# OnOnfre_dual_mola_ssr_rev3_2.net
KiCad netlist of a schematic drawn in EAGLE
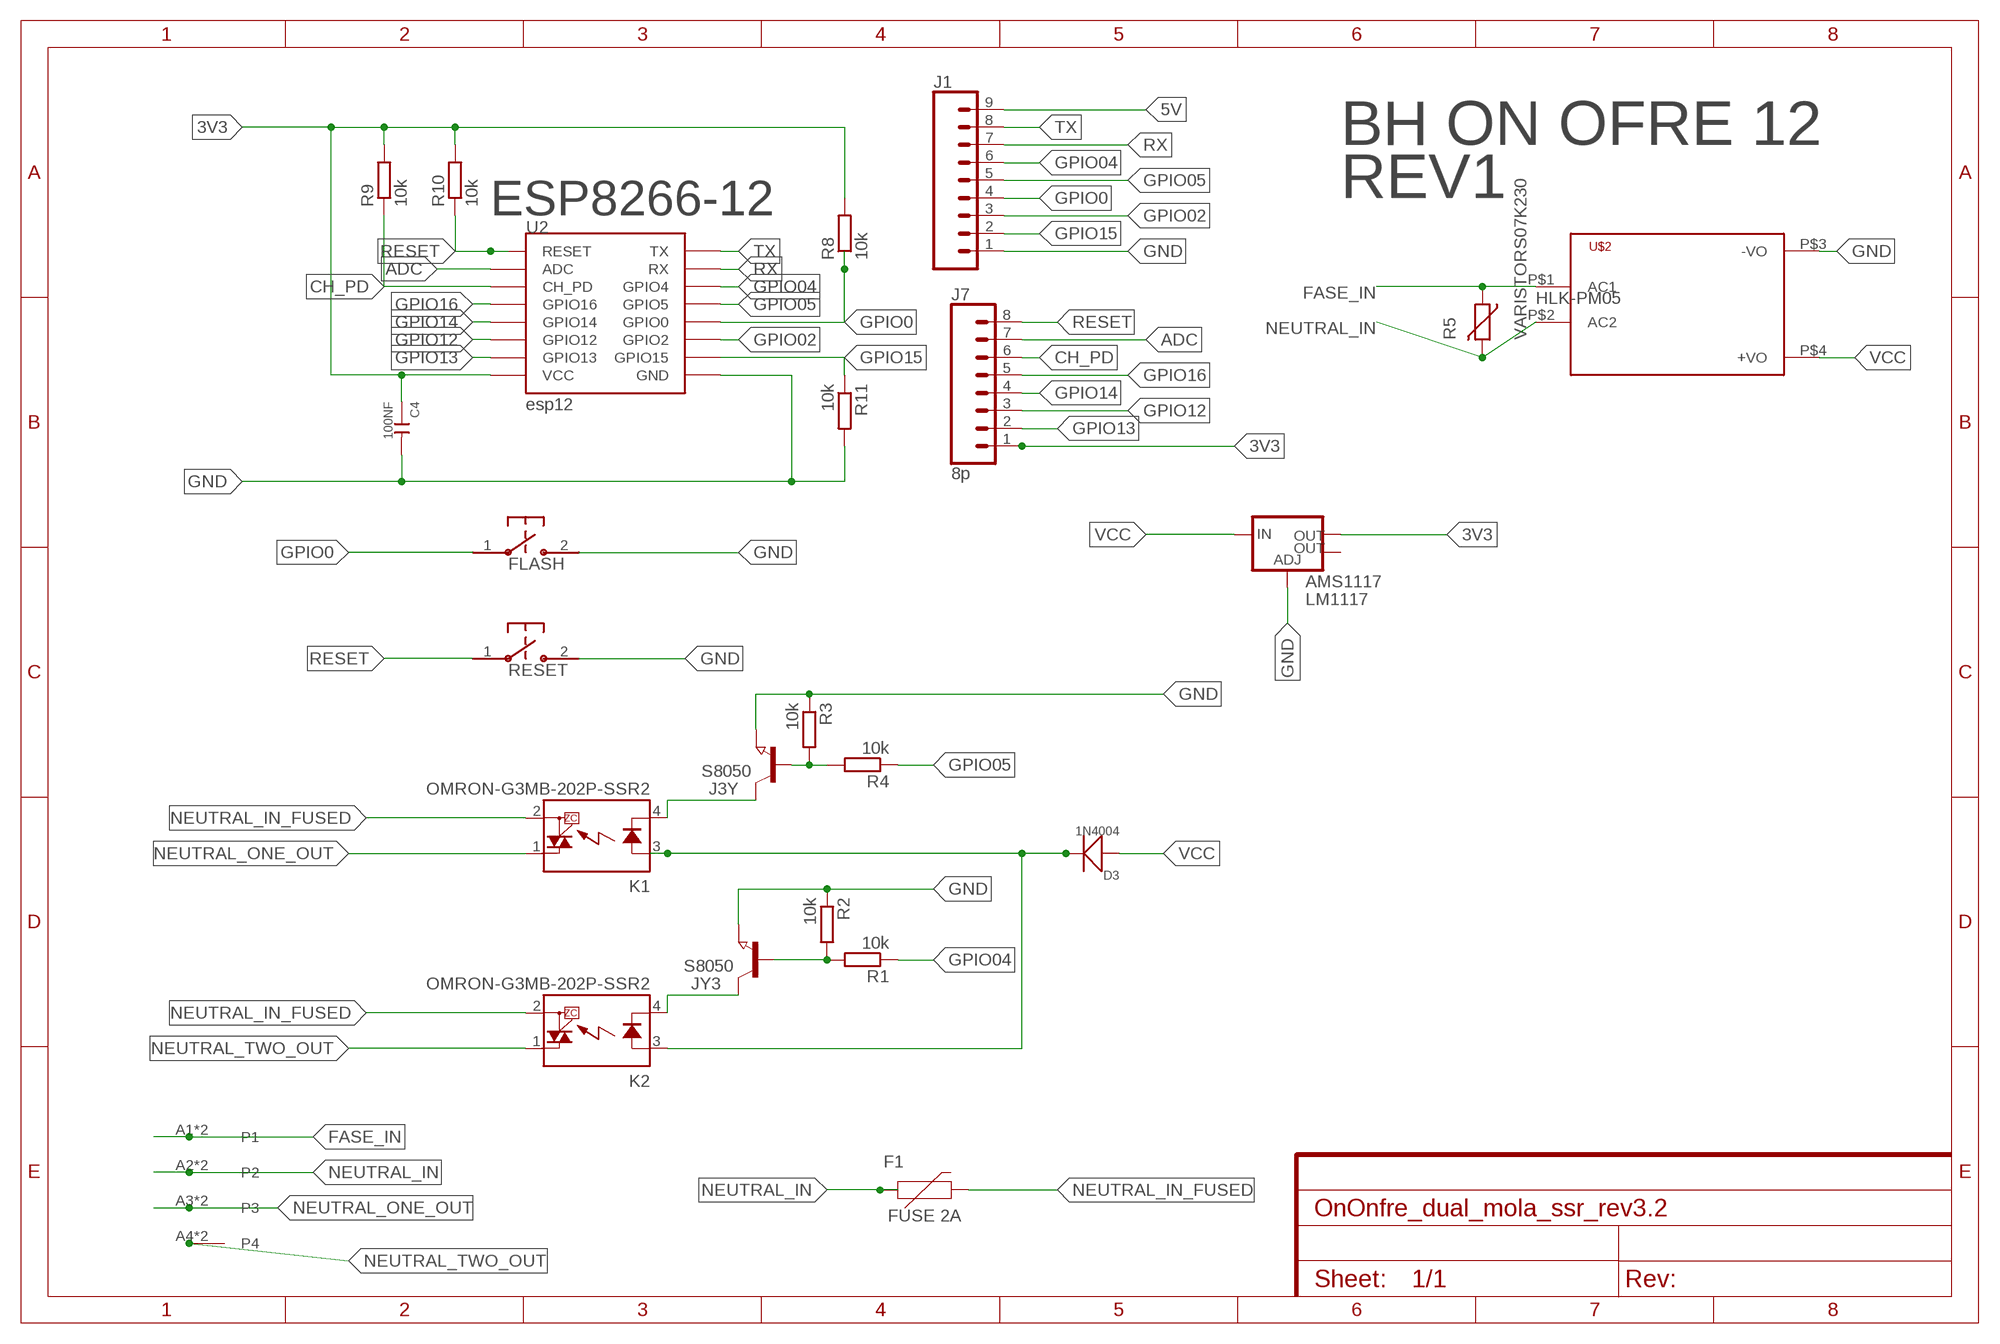
[diagram p0: schematic, sheet 1]

(export (version "E")
  (design (tool "Eeschema 10.0.6"))
  (components
    (comp (ref "AMS1117")
      (value "LM1117")
      (footprint "eagle-import:SOT223")
      (libsource (lib "eagle-import") (part "V_REG_LM1117SOT223"))
    )
    (comp (ref "C4")
      (value "100NF")
      (footprint "eagle-import:C1206")
      (fields (field (name "MPN") "CC1206KKX7RCBB102"))
      (libsource (lib "eagle-import") (part "CERAMIC-1NF-1KV-10%-X7R?(1206)"))
    )
    (comp (ref "D3")
      (value "1N4004")
      (footprint "eagle-import:DO-214AC")
      (fields (field (name "MPN") "1N4007"))
      (libsource (lib "eagle-import") (part "DIODE-GEN-PURPOSE-1KV-1A(DO-214AC)"))
    )
    (comp (ref "F1")
      (value "FUSE 2A")
      (footprint "eagle-import:PTH")
      (libsource (lib "eagle-import") (part "PPTC_PTH"))
    )
    (comp (ref "FLASH")
      (value "B3U-1000P-2P-SMD")
      (footprint "eagle-import:B3U-1000P")
      (fields (field (name "MANUFACTURER") "Omron") (field (name "MPN") "B3U-1000P"))
      (libsource (lib "eagle-import") (part "B3U-1000P"))
    )
    (comp (ref "J1")
      (value "CONN_09")
      (footprint "eagle-import:1X09")
      (libsource (lib "eagle-import") (part "CONN_09"))
    )
    (comp (ref "J3Y")
      (value "S8050")
      (footprint "eagle-import:SOT23")
      (libsource (lib "eagle-import") (part "NPN-TRANSISTOR_SOT23"))
    )
    (comp (ref "J7")
      (value "8p")
      (footprint "eagle-import:1X08")
      (libsource (lib "eagle-import") (part "CONN_08{dblquote}"))
    )
    (comp (ref "JY3")
      (value "S8050")
      (footprint "eagle-import:SOT23")
      (libsource (lib "eagle-import") (part "NPN-TRANSISTOR_SOT23"))
    )
    (comp (ref "K1")
      (value "OMRON-G3MB-202P-SSR2")
      (footprint "eagle-import:OMRON-G3MB-202P-SSR")
      (fields (field (name "MPN") "S202S02F"))
      (libsource (lib "eagle-import") (part "OMRON-G3MB-202P-SSR2"))
    )
    (comp (ref "K2")
      (value "OMRON-G3MB-202P-SSR2")
      (footprint "eagle-import:OMRON-G3MB-202P-SSR")
      (fields (field (name "MPN") "S202S02F"))
      (libsource (lib "eagle-import") (part "OMRON-G3MB-202P-SSR2"))
    )
    (comp (ref "R1")
      (value "10k")
      (footprint "eagle-import:R0603")
      (libsource (lib "eagle-import") (part "R-EU_R0603"))
    )
    (comp (ref "R2")
      (value "10k")
      (footprint "eagle-import:R0603")
      (libsource (lib "eagle-import") (part "R-EU_R0603"))
    )
    (comp (ref "R3")
      (value "10k")
      (footprint "eagle-import:R0603")
      (libsource (lib "eagle-import") (part "R-EU_R0603"))
    )
    (comp (ref "R4")
      (value "10k")
      (footprint "eagle-import:R0603")
      (libsource (lib "eagle-import") (part "R-EU_R0603"))
    )
    (comp (ref "R5")
      (value "VARISTORS07K230")
      (footprint "eagle-import:S07K230")
      (libsource (lib "eagle-import") (part "VARISTORS07K230"))
    )
    (comp (ref "R8")
      (value "10k")
      (footprint "eagle-import:R0603")
      (libsource (lib "eagle-import") (part "R-EU_R0603"))
    )
    (comp (ref "R9")
      (value "10k")
      (footprint "eagle-import:R0603")
      (libsource (lib "eagle-import") (part "R-EU_R0603"))
    )
    (comp (ref "R10")
      (value "10k")
      (footprint "eagle-import:R0603")
      (libsource (lib "eagle-import") (part "R-EU_R0603"))
    )
    (comp (ref "R11")
      (value "10k")
      (footprint "eagle-import:R0603")
      (libsource (lib "eagle-import") (part "R-EU_R0603"))
    )
    (comp (ref "RESET")
      (value "B3U-1000P-2P-SMD")
      (footprint "eagle-import:B3U-1000P")
      (fields (field (name "MANUFACTURER") "Omron") (field (name "MPN") "B3U-1000P"))
      (libsource (lib "eagle-import") (part "B3U-1000P"))
    )
    (comp (ref "U$1")
      (value "4P4P")
      (footprint "eagle-import:4P")
      (libsource (lib "eagle-import") (part "4P4P"))
    )
    (comp (ref "U$2")
      (value "HKLPM01")
      (footprint "eagle-import:HKLPM01")
      (libsource (lib "eagle-import") (part "HKLPM01"))
    )
    (comp (ref "U2")
      (value "esp12")
      (footprint "eagle-import:ESP12-SMD")
      (libsource (lib "eagle-import") (part "ESP12SMD"))
    )
  )
  (nets
    (net (code "1") (name "3V3") (class "Default")
      (node (ref "AMS1117") (pin "2") (pinfunction "OUT_2") (pintype "output"))
      (node (ref "C4") (pin "1") (pinfunction "1_1") (pintype "passive"))
      (node (ref "J7") (pin "1") (pinfunction "1_1") (pintype "passive"))
      (node (ref "R10") (pin "2") (pinfunction "2_2") (pintype "passive"))
      (node (ref "R8") (pin "2") (pinfunction "2_2") (pintype "passive"))
      (node (ref "R9") (pin "2") (pinfunction "2_2") (pintype "passive"))
      (node (ref "U2") (pin "VCC") (pinfunction "VCC_VCC") (pintype "bidirectional"))
    )
    (net (code "2") (name "5V") (class "Default")
      (node (ref "D3") (pin "2") (pinfunction "-_2") (pintype "passive"))
      (node (ref "J1") (pin "9") (pinfunction "9_9") (pintype "passive"))
      (node (ref "K1") (pin "3") (pinfunction "A_3") (pintype "passive"))
      (node (ref "K2") (pin "3") (pinfunction "A_3") (pintype "passive"))
    )
    (net (code "3") (name "ADC") (class "Default")
      (node (ref "J7") (pin "7") (pinfunction "7_7") (pintype "passive"))
      (node (ref "U2") (pin "ADC") (pinfunction "ADC_ADC") (pintype "bidirectional"))
    )
    (net (code "4") (name "CH_PD") (class "Default")
      (node (ref "J7") (pin "6") (pinfunction "6_6") (pintype "passive"))
      (node (ref "R9") (pin "1") (pinfunction "1_1") (pintype "passive"))
      (node (ref "U2") (pin "CH_PD") (pinfunction "CH_PD_CH_PD") (pintype "bidirectional"))
    )
    (net (code "5") (name "FASE_IN") (class "Default")
      (node (ref "R5") (pin "1") (pinfunction "1_1") (pintype "passive"))
      (node (ref "U$1") (pin "A1") (pinfunction "P1_A1") (pintype "bidirectional"))
      (node (ref "U$1") (pin "B1") (pinfunction "P1_B1") (pintype "bidirectional"))
      (node (ref "U$2") (pin "P$1") (pinfunction "AC1_P$1") (pintype "bidirectional"))
    )
    (net (code "6") (name "GND") (class "Default")
      (node (ref "AMS1117") (pin "1") (pinfunction "ADJ_1") (pintype "input"))
      (node (ref "C4") (pin "2") (pinfunction "2_2") (pintype "passive"))
      (node (ref "FLASH") (pin "2") (pinfunction "P$2_2") (pintype "passive"))
      (node (ref "J1") (pin "1") (pinfunction "1_1") (pintype "passive"))
      (node (ref "J3Y") (pin "2") (pinfunction "E_2") (pintype "passive"))
      (node (ref "JY3") (pin "2") (pinfunction "E_2") (pintype "passive"))
      (node (ref "R11") (pin "2") (pinfunction "2_2") (pintype "passive"))
      (node (ref "R2") (pin "1") (pinfunction "1_1") (pintype "passive"))
      (node (ref "R3") (pin "1") (pinfunction "1_1") (pintype "passive"))
      (node (ref "RESET") (pin "2") (pinfunction "P$2_2") (pintype "passive"))
      (node (ref "U$2") (pin "P$3") (pinfunction "-VO_P$3") (pintype "bidirectional"))
      (node (ref "U2") (pin "GND") (pinfunction "GND_GND") (pintype "bidirectional"))
    )
    (net (code "7") (name "GPIO0") (class "Default")
      (node (ref "FLASH") (pin "1") (pinfunction "P$1_1") (pintype "passive"))
      (node (ref "J1") (pin "4") (pinfunction "4_4") (pintype "passive"))
      (node (ref "R8") (pin "1") (pinfunction "1_1") (pintype "passive"))
      (node (ref "U2") (pin "GPIO0") (pinfunction "GPIO0_GPIO0") (pintype "bidirectional"))
    )
    (net (code "8") (name "GPIO02") (class "Default")
      (node (ref "J1") (pin "3") (pinfunction "3_3") (pintype "passive"))
      (node (ref "U2") (pin "GPIO2") (pinfunction "GPIO2_GPIO2") (pintype "bidirectional"))
    )
    (net (code "9") (name "GPIO04") (class "Default")
      (node (ref "J1") (pin "6") (pinfunction "6_6") (pintype "passive"))
      (node (ref "R1") (pin "1") (pinfunction "1_1") (pintype "passive"))
      (node (ref "U2") (pin "GPIO4") (pinfunction "GPIO4_GPIO4") (pintype "bidirectional"))
    )
    (net (code "10") (name "GPIO05") (class "Default")
      (node (ref "J1") (pin "5") (pinfunction "5_5") (pintype "passive"))
      (node (ref "R4") (pin "1") (pinfunction "1_1") (pintype "passive"))
      (node (ref "U2") (pin "GPIO5") (pinfunction "GPIO5_GPIO5") (pintype "bidirectional"))
    )
    (net (code "11") (name "GPIO12") (class "Default")
      (node (ref "J7") (pin "3") (pinfunction "3_3") (pintype "passive"))
      (node (ref "U2") (pin "GPIO12") (pinfunction "GPIO12_GPIO12") (pintype "bidirectional"))
    )
    (net (code "12") (name "GPIO13") (class "Default")
      (node (ref "J7") (pin "2") (pinfunction "2_2") (pintype "passive"))
      (node (ref "U2") (pin "GPIO13") (pinfunction "GPIO13_GPIO13") (pintype "bidirectional"))
    )
    (net (code "13") (name "GPIO14") (class "Default")
      (node (ref "J7") (pin "4") (pinfunction "4_4") (pintype "passive"))
      (node (ref "U2") (pin "GPIO14") (pinfunction "GPIO14_GPIO14") (pintype "bidirectional"))
    )
    (net (code "14") (name "GPIO15") (class "Default")
      (node (ref "J1") (pin "2") (pinfunction "2_2") (pintype "passive"))
      (node (ref "R11") (pin "1") (pinfunction "1_1") (pintype "passive"))
      (node (ref "U2") (pin "GPIO15") (pinfunction "GPIO15_GPIO15") (pintype "bidirectional"))
    )
    (net (code "15") (name "GPIO16") (class "Default")
      (node (ref "J7") (pin "5") (pinfunction "5_5") (pintype "passive"))
      (node (ref "U2") (pin "GPIO16") (pinfunction "GPIO16_GPIO16") (pintype "bidirectional"))
    )
    (net (code "16") (name "NEUTRAL_IN") (class "Default")
      (node (ref "F1") (pin "P$1") (pinfunction "1_P$1") (pintype "bidirectional"))
      (node (ref "R5") (pin "2") (pinfunction "2_2") (pintype "passive"))
      (node (ref "U$1") (pin "A2") (pinfunction "P2_A2") (pintype "bidirectional"))
      (node (ref "U$1") (pin "B2") (pinfunction "P2_B2") (pintype "bidirectional"))
      (node (ref "U$2") (pin "P$2") (pinfunction "AC2_P$2") (pintype "bidirectional"))
    )
    (net (code "17") (name "NEUTRAL_IN_FUSED") (class "Default")
      (node (ref "F1") (pin "P$2") (pinfunction "2_P$2") (pintype "bidirectional"))
      (node (ref "K1") (pin "2") (pinfunction "DS2_2") (pintype "passive"))
      (node (ref "K2") (pin "2") (pinfunction "DS2_2") (pintype "passive"))
    )
    (net (code "18") (name "NEUTRAL_ONE_OUT") (class "Default")
      (node (ref "K1") (pin "1") (pinfunction "DS1_1") (pintype "passive"))
      (node (ref "U$1") (pin "A3") (pinfunction "P3_A3") (pintype "bidirectional"))
      (node (ref "U$1") (pin "B3") (pinfunction "P3_B3") (pintype "bidirectional"))
    )
    (net (code "19") (name "NEUTRAL_TWO_OUT") (class "Default")
      (node (ref "K2") (pin "1") (pinfunction "DS1_1") (pintype "passive"))
      (node (ref "U$1") (pin "A4") (pinfunction "P4_A4") (pintype "bidirectional"))
      (node (ref "U$1") (pin "B4") (pinfunction "P4_B4") (pintype "bidirectional"))
    )
    (net (code "20") (name "Net-(J3Y-B)") (class "Default")
      (node (ref "J3Y") (pin "1") (pinfunction "B_1") (pintype "passive"))
      (node (ref "R3") (pin "2") (pinfunction "2_2") (pintype "passive"))
      (node (ref "R4") (pin "2") (pinfunction "2_2") (pintype "passive"))
    )
    (net (code "21") (name "Net-(J3Y-C)") (class "Default")
      (node (ref "J3Y") (pin "3") (pinfunction "C_3") (pintype "passive"))
      (node (ref "K1") (pin "4") (pinfunction "K_4") (pintype "passive"))
    )
    (net (code "22") (name "Net-(JY3-B)") (class "Default")
      (node (ref "JY3") (pin "1") (pinfunction "B_1") (pintype "passive"))
      (node (ref "R1") (pin "2") (pinfunction "2_2") (pintype "passive"))
      (node (ref "R2") (pin "2") (pinfunction "2_2") (pintype "passive"))
    )
    (net (code "23") (name "Net-(JY3-C)") (class "Default")
      (node (ref "JY3") (pin "3") (pinfunction "C_3") (pintype "passive"))
      (node (ref "K2") (pin "4") (pinfunction "K_4") (pintype "passive"))
    )
    (net (code "24") (name "RESET") (class "Default")
      (node (ref "J7") (pin "8") (pinfunction "8_8") (pintype "passive"))
      (node (ref "R10") (pin "1") (pinfunction "1_1") (pintype "passive"))
      (node (ref "RESET") (pin "1") (pinfunction "P$1_1") (pintype "passive"))
      (node (ref "U2") (pin "RESET") (pinfunction "RESET_RESET") (pintype "bidirectional"))
    )
    (net (code "25") (name "RX") (class "Default")
      (node (ref "J1") (pin "7") (pinfunction "7_7") (pintype "passive"))
      (node (ref "U2") (pin "RXD0") (pinfunction "RX_RXD0") (pintype "bidirectional"))
    )
    (net (code "26") (name "TX") (class "Default")
      (node (ref "J1") (pin "8") (pinfunction "8_8") (pintype "passive"))
      (node (ref "U2") (pin "TXD0") (pinfunction "TX_TXD0") (pintype "bidirectional"))
    )
    (net (code "27") (name "VCC") (class "Default")
      (node (ref "AMS1117") (pin "3") (pinfunction "IN_3") (pintype "input"))
      (node (ref "D3") (pin "1") (pinfunction "+_1") (pintype "passive"))
      (node (ref "U$2") (pin "P$4") (pinfunction "+VO_P$4") (pintype "bidirectional"))
    )
    (net (code "28") (name "unconnected-(AMS1117-OUT-Pad4)") (class "Default")
      (node (ref "AMS1117") (pin "4") (pinfunction "OUT_4") (pintype "output"))
    )
  )
)
